# Kopfh_rerverst_rker_DAC_Board_CP2114_Rev.net
KiCad netlist of a schematic drawn in EAGLE
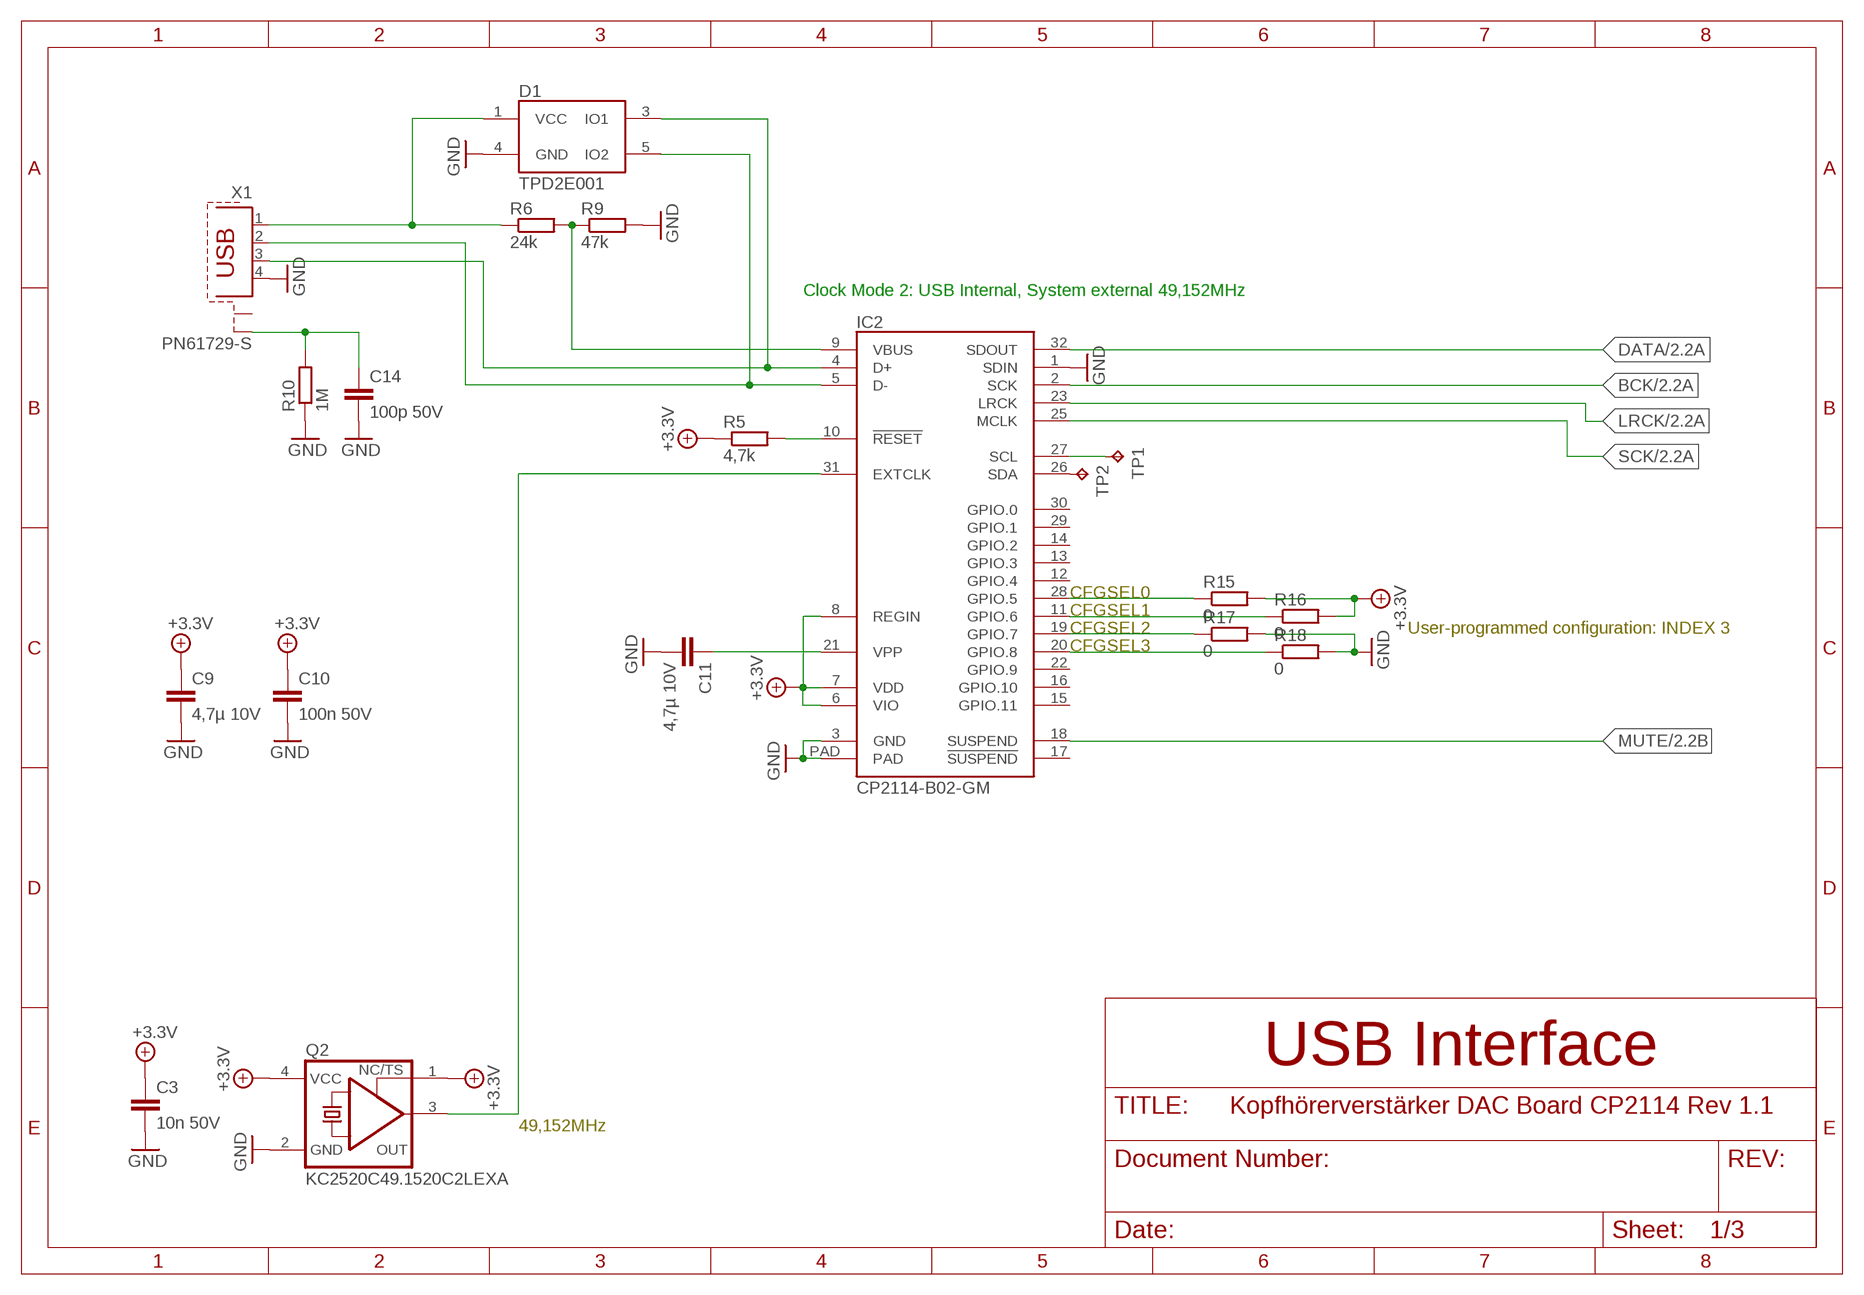
[diagram p0: schematic, sheet 1]
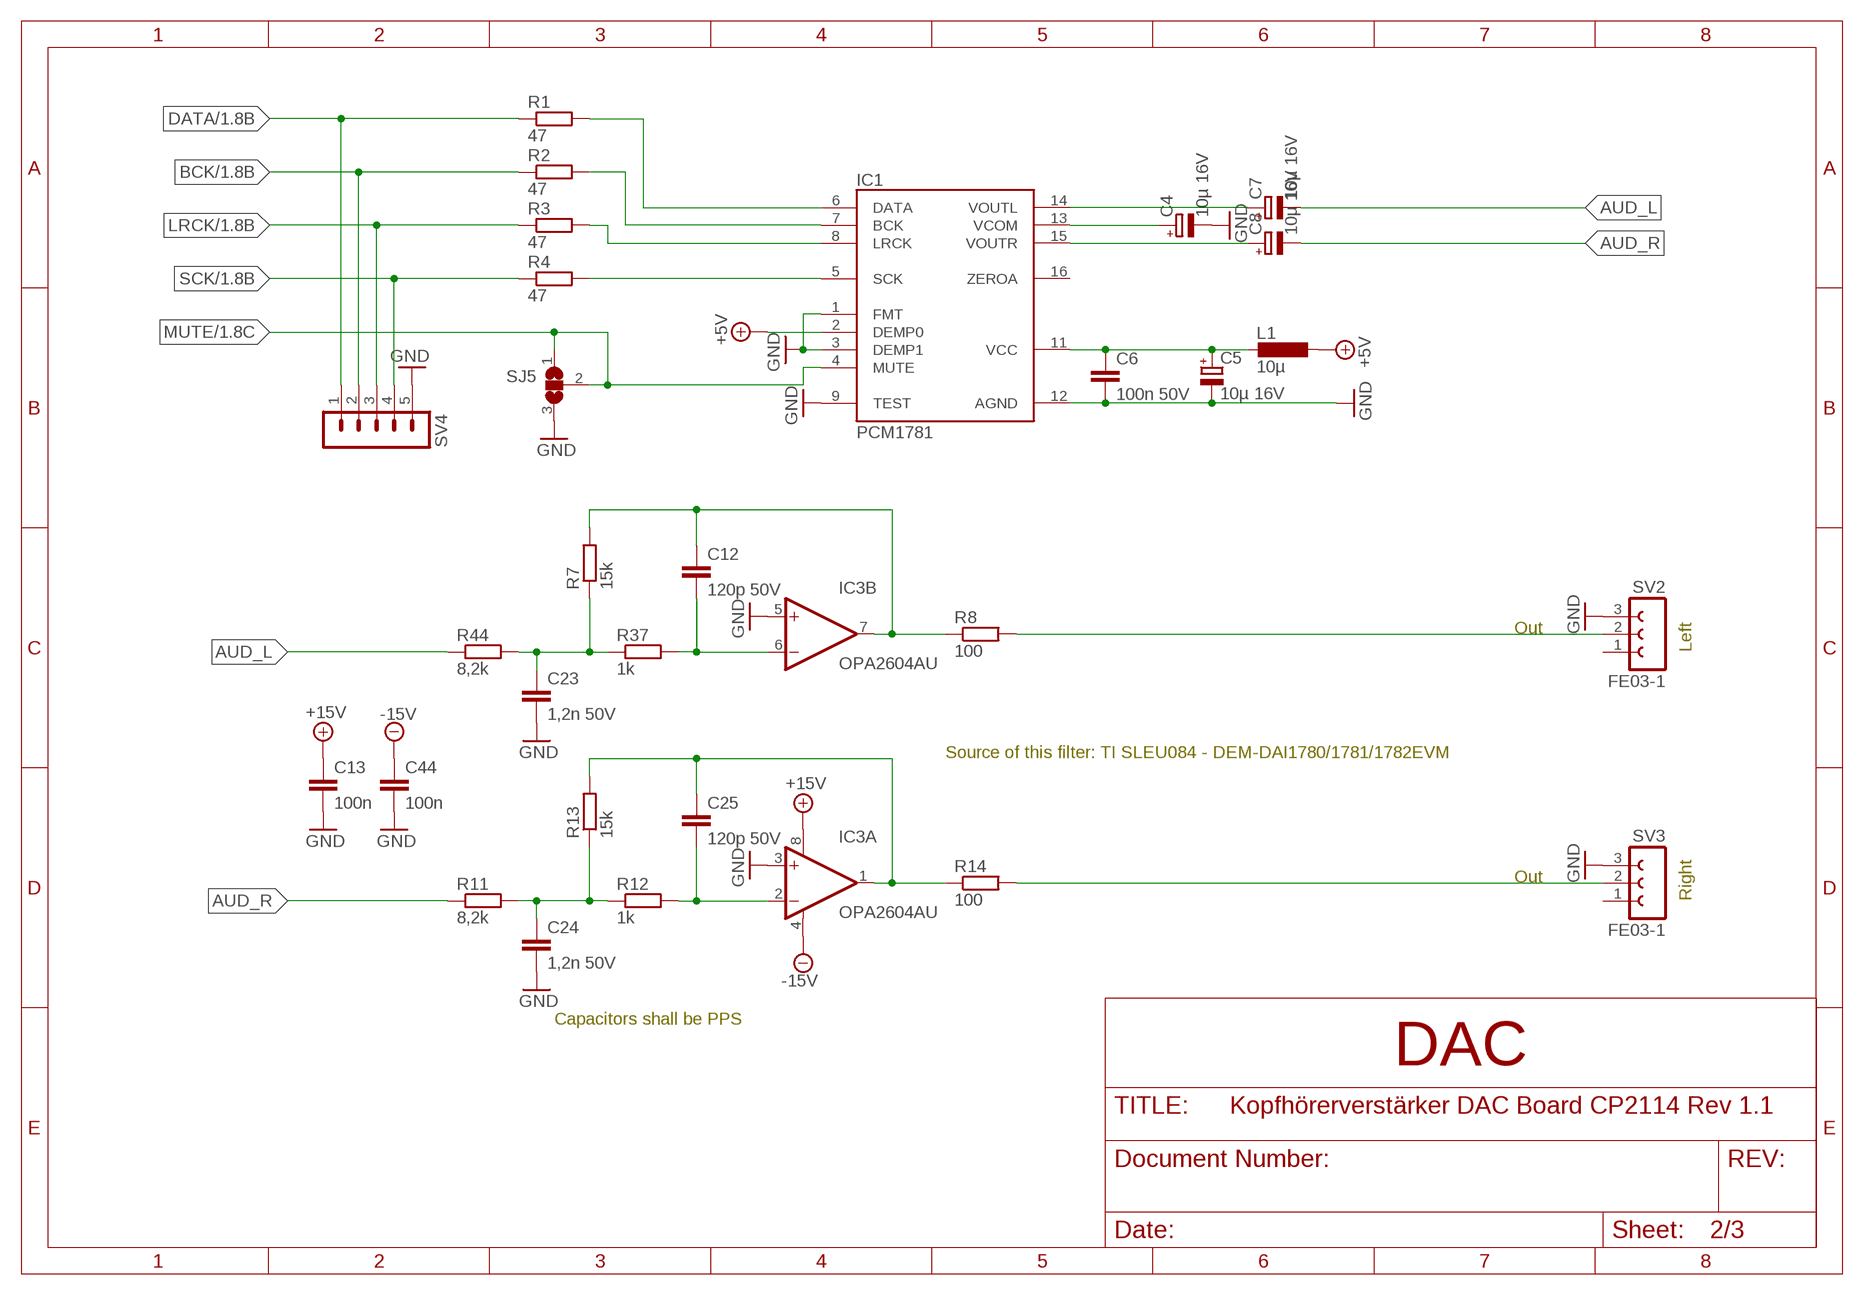
[diagram p1: schematic, sheet 2]
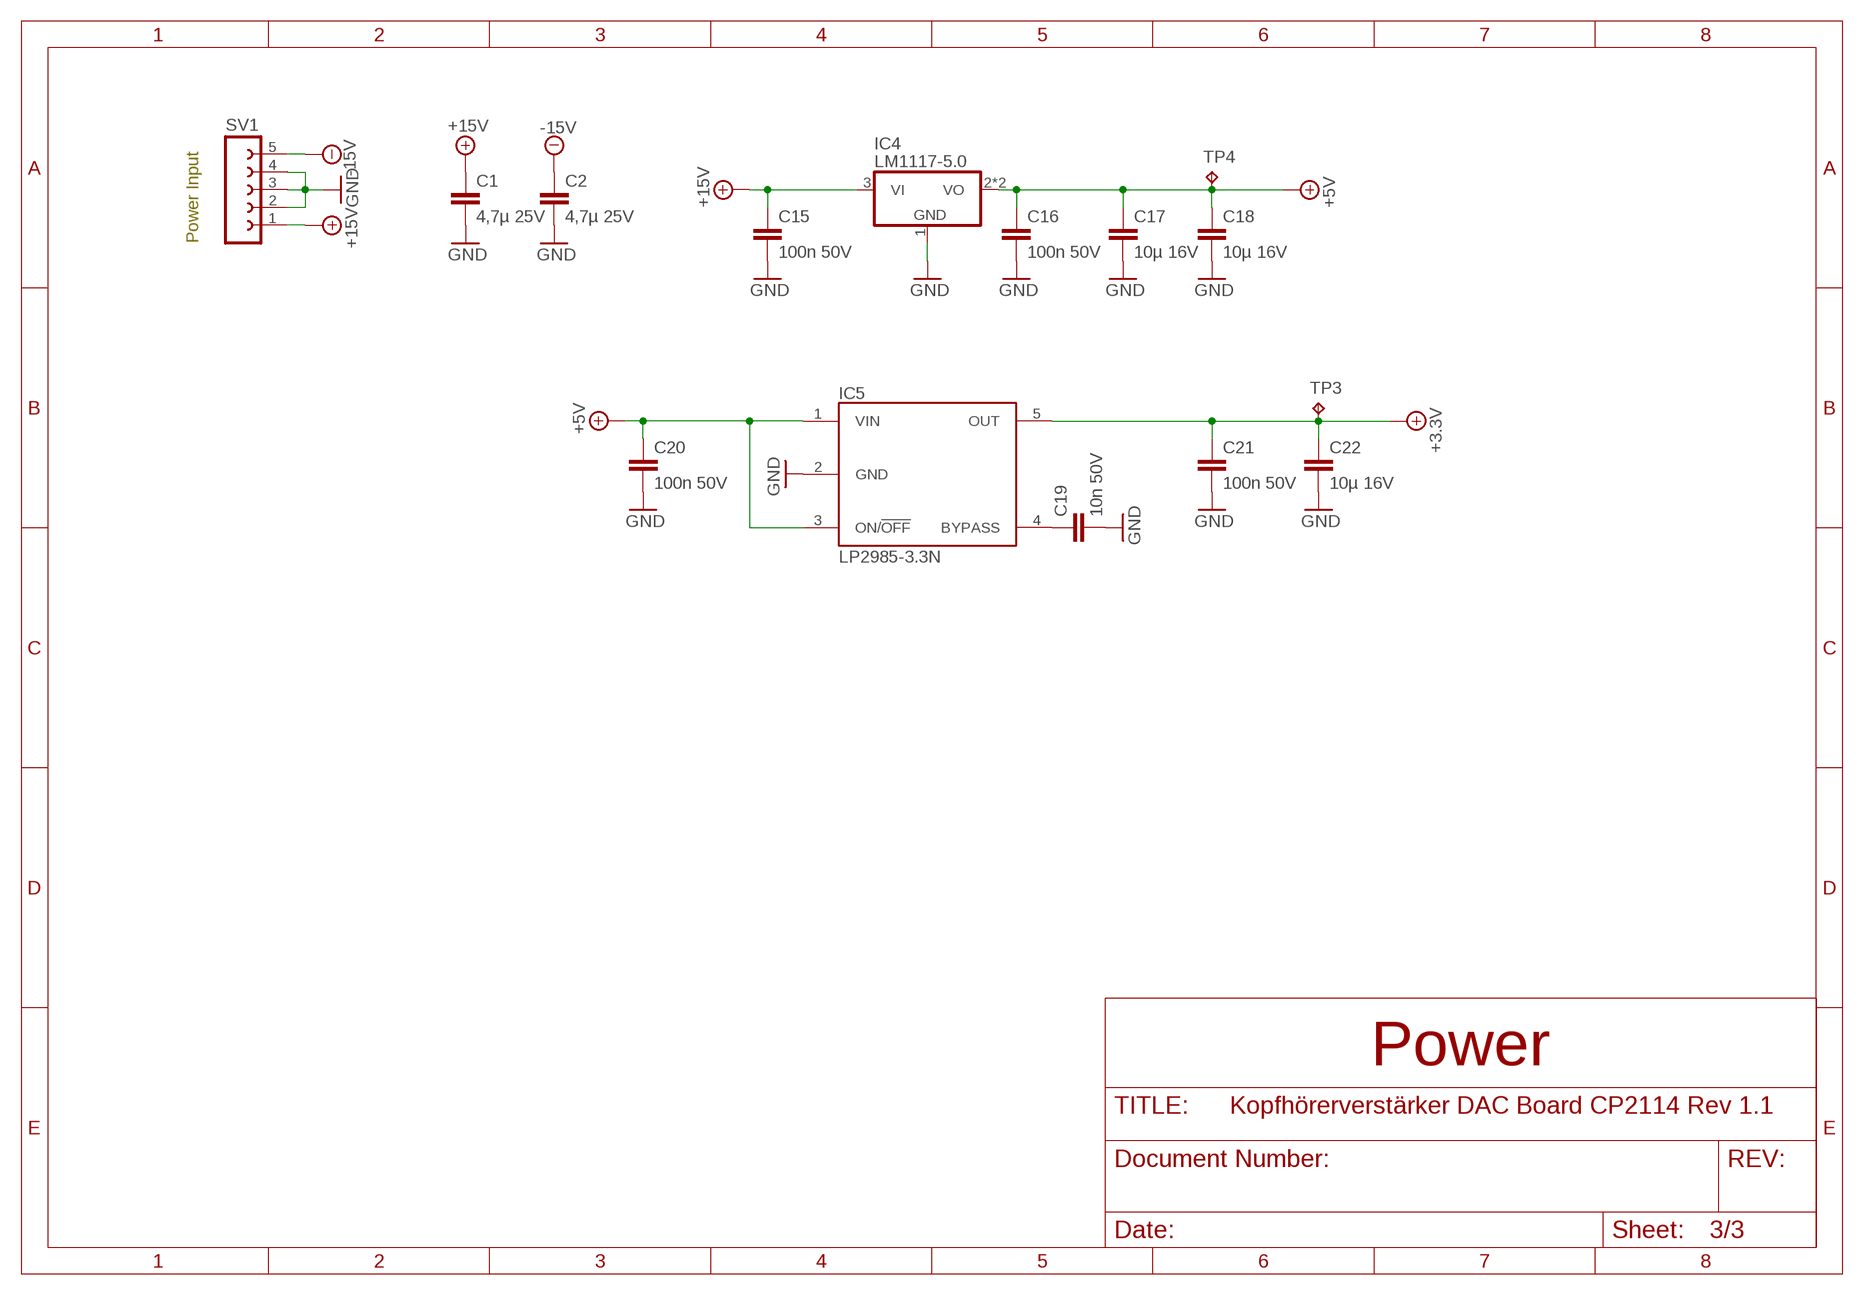
[diagram p2: schematic, sheet 3]

(export (version "E")
  (design (tool "Eeschema 10.0.6"))
  (components
    (comp (ref "C3")
      (value "10n 50V")
      (footprint "eagle-import:C0805")
      (libsource (lib "eagle-import") (part "C-EUC0805"))
    )
    (comp (ref "C9")
      (value "4,7µ 10V")
      (footprint "eagle-import:C0805")
      (libsource (lib "eagle-import") (part "C-EUC0805"))
    )
    (comp (ref "C10")
      (value "100n 50V")
      (footprint "eagle-import:C0805")
      (libsource (lib "eagle-import") (part "C-EUC0805"))
    )
    (comp (ref "C11")
      (value "4,7µ 10V")
      (footprint "eagle-import:C0805")
      (libsource (lib "eagle-import") (part "C-EUC0805"))
    )
    (comp (ref "C14")
      (value "100p 50V")
      (footprint "eagle-import:C0805")
      (libsource (lib "eagle-import") (part "C-EUC0805"))
    )
    (comp (ref "D1")
      (value "TPD2E001")
      (footprint "eagle-import:SOT-5X3_R-PDSO-N5-DRL")
      (libsource (lib "eagle-import") (part "TPD2E001"))
    )
    (comp (ref "IC2")
      (value "CP2114-B02-GM")
      (footprint "eagle-import:QFN32")
      (libsource (lib "eagle-import") (part "CP2114-B02-GM"))
    )
    (comp (ref "Q2")
      (value "KC2520C49.1520C2LEXA")
      (footprint "eagle-import:2.5X2.0")
      (libsource (lib "eagle-import") (part "XO-2,5X2,0"))
    )
    (comp (ref "R5")
      (value "4,7k")
      (footprint "eagle-import:R0805")
      (libsource (lib "eagle-import") (part "R-EU_R0805"))
    )
    (comp (ref "R6")
      (value "24k")
      (footprint "eagle-import:R0805")
      (libsource (lib "eagle-import") (part "R-EU_R0805"))
    )
    (comp (ref "R9")
      (value "47k")
      (footprint "eagle-import:R0805")
      (libsource (lib "eagle-import") (part "R-EU_R0805"))
    )
    (comp (ref "R10")
      (value "1M")
      (footprint "eagle-import:R0805")
      (libsource (lib "eagle-import") (part "R-EU_R0805"))
    )
    (comp (ref "R15")
      (value "0")
      (footprint "eagle-import:R0805")
      (libsource (lib "eagle-import") (part "R-EU_R0805"))
    )
    (comp (ref "R16")
      (value "0")
      (footprint "eagle-import:R0805")
      (libsource (lib "eagle-import") (part "R-EU_R0805"))
    )
    (comp (ref "R17")
      (value "0")
      (footprint "eagle-import:R0805")
      (libsource (lib "eagle-import") (part "R-EU_R0805"))
    )
    (comp (ref "R18")
      (value "0")
      (footprint "eagle-import:R0805")
      (libsource (lib "eagle-import") (part "R-EU_R0805"))
    )
    (comp (ref "TP1")
      (value "TPTP10R")
      (footprint "eagle-import:TP10R")
      (libsource (lib "eagle-import") (part "TPTP10R"))
    )
    (comp (ref "TP2")
      (value "TPTP10R")
      (footprint "eagle-import:TP10R")
      (libsource (lib "eagle-import") (part "TPTP10R"))
    )
    (comp (ref "X1")
      (value "PN61729-S")
      (footprint "eagle-import:PN61729-S")
      (libsource (lib "eagle-import") (part "PN61729-S"))
    )
    (comp (ref "C1")
      (value "4,7µ 25V")
      (footprint "eagle-import:C0805")
      (libsource (lib "eagle-import") (part "C-EUC0805"))
    )
    (comp (ref "C2")
      (value "4,7µ 25V")
      (footprint "eagle-import:C0805")
      (libsource (lib "eagle-import") (part "C-EUC0805"))
    )
    (comp (ref "C15")
      (value "100n 50V")
      (footprint "eagle-import:C0805")
      (libsource (lib "eagle-import") (part "C-EUC0805"))
    )
    (comp (ref "C16")
      (value "100n 50V")
      (footprint "eagle-import:C0805")
      (libsource (lib "eagle-import") (part "C-EUC0805"))
    )
    (comp (ref "C17")
      (value "10µ 16V")
      (footprint "eagle-import:C0805")
      (libsource (lib "eagle-import") (part "C-EUC0805"))
    )
    (comp (ref "C18")
      (value "10µ 16V")
      (footprint "eagle-import:C0805")
      (libsource (lib "eagle-import") (part "C-EUC0805"))
    )
    (comp (ref "C19")
      (value "10n 50V")
      (footprint "eagle-import:C0805")
      (libsource (lib "eagle-import") (part "C-EUC0805"))
    )
    (comp (ref "C20")
      (value "100n 50V")
      (footprint "eagle-import:C0805")
      (libsource (lib "eagle-import") (part "C-EUC0805"))
    )
    (comp (ref "C21")
      (value "100n 50V")
      (footprint "eagle-import:C0805")
      (libsource (lib "eagle-import") (part "C-EUC0805"))
    )
    (comp (ref "C22")
      (value "10µ 16V")
      (footprint "eagle-import:C0805")
      (libsource (lib "eagle-import") (part "C-EUC0805"))
    )
    (comp (ref "IC4")
      (value "LM1117-5.0")
      (footprint "eagle-import:SOT223")
      (libsource (lib "eagle-import") (part "LM1117-5.0"))
    )
    (comp (ref "IC5")
      (value "LP2985-3.3N")
      (footprint "eagle-import:SOT23-DBV")
      (libsource (lib "eagle-import") (part "LP2985N-3.3"))
    )
    (comp (ref "SV1")
      (value "FE05-1")
      (footprint "eagle-import:FE05-1")
      (libsource (lib "eagle-import") (part "FE05-1"))
    )
    (comp (ref "TP3")
      (value "TPTP15R")
      (footprint "eagle-import:TP15R")
      (libsource (lib "eagle-import") (part "TPTP15R"))
    )
    (comp (ref "TP4")
      (value "TPTP15R")
      (footprint "eagle-import:TP15R")
      (libsource (lib "eagle-import") (part "TPTP15R"))
    )
    (comp (ref "C4")
      (value "10µ 16V")
      (footprint "eagle-import:E2,5-5")
      (libsource (lib "eagle-import") (part "CPOL-EUE2.5-5"))
    )
    (comp (ref "C5")
      (value "10µ 16V")
      (footprint "eagle-import:E2,5-5")
      (libsource (lib "eagle-import") (part "CPOL-EUE2.5-5"))
    )
    (comp (ref "C6")
      (value "100n 50V")
      (footprint "eagle-import:C0805")
      (libsource (lib "eagle-import") (part "C-EUC0805"))
    )
    (comp (ref "C7")
      (value "10µ 16V")
      (footprint "eagle-import:E2,5-5")
      (libsource (lib "eagle-import") (part "CPOL-EUE2.5-5"))
    )
    (comp (ref "C8")
      (value "10µ 16V")
      (footprint "eagle-import:E2,5-5")
      (libsource (lib "eagle-import") (part "CPOL-EUE2.5-5"))
    )
    (comp (ref "C12")
      (value "120p 50V")
      (footprint "eagle-import:C0805")
      (libsource (lib "eagle-import") (part "C-EUC0805"))
    )
    (comp (ref "C13")
      (value "100n")
      (footprint "eagle-import:C0805")
      (libsource (lib "eagle-import") (part "C-EUC0805"))
    )
    (comp (ref "C23")
      (value "1,2n 50V")
      (footprint "eagle-import:C0805")
      (libsource (lib "eagle-import") (part "C-EUC0805"))
    )
    (comp (ref "C24")
      (value "1,2n 50V")
      (footprint "eagle-import:C0805")
      (libsource (lib "eagle-import") (part "C-EUC0805"))
    )
    (comp (ref "C25")
      (value "120p 50V")
      (footprint "eagle-import:C0805")
      (libsource (lib "eagle-import") (part "C-EUC0805"))
    )
    (comp (ref "C44")
      (value "100n")
      (footprint "eagle-import:C0805")
      (libsource (lib "eagle-import") (part "C-EUC0805"))
    )
    (comp (ref "IC1")
      (value "PCM1781")
      (footprint "eagle-import:PW_R-PDSO-G16")
      (libsource (lib "eagle-import") (part "PCM1781"))
    )
    (comp (ref "IC3")
      (value "OPA2604AU")
      (footprint "eagle-import:SO08")
      (libsource (lib "eagle-import") (part "OPA2604AU"))
    )
    (comp (ref "L1")
      (value "10µ")
      (footprint "eagle-import:L0805")
      (libsource (lib "eagle-import") (part "L-EUL0805"))
    )
    (comp (ref "R1")
      (value "47")
      (footprint "eagle-import:R0805")
      (libsource (lib "eagle-import") (part "R-EU_R0805"))
    )
    (comp (ref "R2")
      (value "47")
      (footprint "eagle-import:R0805")
      (libsource (lib "eagle-import") (part "R-EU_R0805"))
    )
    (comp (ref "R3")
      (value "47")
      (footprint "eagle-import:R0805")
      (libsource (lib "eagle-import") (part "R-EU_R0805"))
    )
    (comp (ref "R4")
      (value "47")
      (footprint "eagle-import:R0805")
      (libsource (lib "eagle-import") (part "R-EU_R0805"))
    )
    (comp (ref "R7")
      (value "15k")
      (footprint "eagle-import:R0805")
      (libsource (lib "eagle-import") (part "R-EU_R0805"))
    )
    (comp (ref "R8")
      (value "100")
      (footprint "eagle-import:R0805")
      (libsource (lib "eagle-import") (part "R-EU_R0805"))
    )
    (comp (ref "R11")
      (value "8,2k")
      (footprint "eagle-import:R0805")
      (libsource (lib "eagle-import") (part "R-EU_R0805"))
    )
    (comp (ref "R12")
      (value "1k")
      (footprint "eagle-import:R0805")
      (libsource (lib "eagle-import") (part "R-EU_R0805"))
    )
    (comp (ref "R13")
      (value "15k")
      (footprint "eagle-import:R0805")
      (libsource (lib "eagle-import") (part "R-EU_R0805"))
    )
    (comp (ref "R14")
      (value "100")
      (footprint "eagle-import:R0805")
      (libsource (lib "eagle-import") (part "R-EU_R0805"))
    )
    (comp (ref "R37")
      (value "1k")
      (footprint "eagle-import:R0805")
      (libsource (lib "eagle-import") (part "R-EU_R0805"))
    )
    (comp (ref "R44")
      (value "8,2k")
      (footprint "eagle-import:R0805")
      (libsource (lib "eagle-import") (part "R-EU_R0805"))
    )
    (comp (ref "SJ5")
      (value "SJ2W")
      (footprint "eagle-import:SJ_2")
      (libsource (lib "eagle-import") (part "SJ2W"))
    )
    (comp (ref "SV2")
      (value "FE03-1")
      (footprint "eagle-import:FE03-1")
      (libsource (lib "eagle-import") (part "FE03-1"))
    )
    (comp (ref "SV3")
      (value "FE03-1")
      (footprint "eagle-import:FE03-1")
      (libsource (lib "eagle-import") (part "FE03-1"))
    )
    (comp (ref "SV4")
      (value "MA05-1")
      (footprint "eagle-import:MA05-1")
      (libsource (lib "eagle-import") (part "MA05-1"))
    )
  )
  (nets
    (net (code "1") (name "+3,3V") (class "Default")
      (node (ref "C10") (pin "1") (pinfunction "1_1") (pintype "passive"))
      (node (ref "C21") (pin "1") (pinfunction "1_1") (pintype "passive"))
      (node (ref "C22") (pin "1") (pinfunction "1_1") (pintype "passive"))
      (node (ref "C3") (pin "1") (pinfunction "1_1") (pintype "passive"))
      (node (ref "C9") (pin "1") (pinfunction "1_1") (pintype "passive"))
      (node (ref "IC2") (pin "6") (pinfunction "VIO_6") (pintype "bidirectional"))
      (node (ref "IC2") (pin "7") (pinfunction "VDD_7") (pintype "bidirectional"))
      (node (ref "IC2") (pin "8") (pinfunction "REGIN_8") (pintype "bidirectional"))
      (node (ref "IC5") (pin "5") (pinfunction "OUT_5") (pintype "bidirectional"))
      (node (ref "Q2") (pin "1") (pinfunction "TS_1") (pintype "passive"))
      (node (ref "Q2") (pin "4") (pinfunction "VCC_4") (pintype "power_in"))
      (node (ref "R15") (pin "2") (pinfunction "2_2") (pintype "passive"))
      (node (ref "R16") (pin "2") (pinfunction "2_2") (pintype "passive"))
      (node (ref "R5") (pin "1") (pinfunction "1_1") (pintype "passive"))
      (node (ref "TP3") (pin "TP") (pinfunction "TP_TP") (pintype "input"))
    )
    (net (code "2") (name "+5V") (class "Default")
      (node (ref "C16") (pin "1") (pinfunction "1_1") (pintype "passive"))
      (node (ref "C17") (pin "1") (pinfunction "1_1") (pintype "passive"))
      (node (ref "C18") (pin "1") (pinfunction "1_1") (pintype "passive"))
      (node (ref "C20") (pin "1") (pinfunction "1_1") (pintype "passive"))
      (node (ref "IC1") (pin "2") (pinfunction "DEMP0_2") (pintype "bidirectional"))
      (node (ref "IC4") (pin "2") (pinfunction "VO_2") (pintype "passive"))
      (node (ref "IC4") (pin "4") (pinfunction "VO_4") (pintype "passive"))
      (node (ref "IC5") (pin "1") (pinfunction "VIN_1") (pintype "bidirectional"))
      (node (ref "IC5") (pin "3") (pinfunction "ON/~{OFF}_3") (pintype "bidirectional"))
      (node (ref "L1") (pin "1") (pinfunction "1_1") (pintype "passive"))
      (node (ref "TP4") (pin "TP") (pinfunction "TP_TP") (pintype "input"))
    )
    (net (code "3") (name "+15V") (class "Default")
      (node (ref "C1") (pin "1") (pinfunction "1_1") (pintype "passive"))
      (node (ref "C13") (pin "1") (pinfunction "1_1") (pintype "passive"))
      (node (ref "C15") (pin "1") (pinfunction "1_1") (pintype "passive"))
      (node (ref "IC3") (pin "8") (pinfunction "V+_8") (pintype "power_in"))
      (node (ref "IC4") (pin "3") (pinfunction "VI_3") (pintype "input"))
      (node (ref "SV1") (pin "1") (pinfunction "1_1") (pintype "passive"))
    )
    (net (code "4") (name "-15V") (class "Default")
      (node (ref "C2") (pin "1") (pinfunction "1_1") (pintype "passive"))
      (node (ref "C44") (pin "1") (pinfunction "1_1") (pintype "passive"))
      (node (ref "IC3") (pin "4") (pinfunction "V-_4") (pintype "power_in"))
      (node (ref "SV1") (pin "5") (pinfunction "5_5") (pintype "passive"))
    )
    (net (code "5") (name "AUD_L") (class "Default")
      (node (ref "C7") (pin "-") (pinfunction "-_-") (pintype "passive"))
      (node (ref "R44") (pin "1") (pinfunction "1_1") (pintype "passive"))
    )
    (net (code "6") (name "AUD_R") (class "Default")
      (node (ref "C8") (pin "-") (pinfunction "-_-") (pintype "passive"))
      (node (ref "R11") (pin "1") (pinfunction "1_1") (pintype "passive"))
    )
    (net (code "7") (name "BCK") (class "Default")
      (node (ref "IC2") (pin "2") (pinfunction "SCK_2") (pintype "bidirectional"))
      (node (ref "R2") (pin "1") (pinfunction "1_1") (pintype "passive"))
      (node (ref "SV4") (pin "2") (pinfunction "2_2") (pintype "passive"))
    )
    (net (code "8") (name "DATA") (class "Default")
      (node (ref "IC2") (pin "32") (pinfunction "SDOUT_32") (pintype "bidirectional"))
      (node (ref "R1") (pin "1") (pinfunction "1_1") (pintype "passive"))
      (node (ref "SV4") (pin "1") (pinfunction "1_1") (pintype "passive"))
    )
    (net (code "9") (name "GND") (class "Default")
      (node (ref "C1") (pin "2") (pinfunction "2_2") (pintype "passive"))
      (node (ref "C10") (pin "2") (pinfunction "2_2") (pintype "passive"))
      (node (ref "C11") (pin "2") (pinfunction "2_2") (pintype "passive"))
      (node (ref "C13") (pin "2") (pinfunction "2_2") (pintype "passive"))
      (node (ref "C14") (pin "2") (pinfunction "2_2") (pintype "passive"))
      (node (ref "C15") (pin "2") (pinfunction "2_2") (pintype "passive"))
      (node (ref "C16") (pin "2") (pinfunction "2_2") (pintype "passive"))
      (node (ref "C17") (pin "2") (pinfunction "2_2") (pintype "passive"))
      (node (ref "C18") (pin "2") (pinfunction "2_2") (pintype "passive"))
      (node (ref "C19") (pin "2") (pinfunction "2_2") (pintype "passive"))
      (node (ref "C2") (pin "2") (pinfunction "2_2") (pintype "passive"))
      (node (ref "C20") (pin "2") (pinfunction "2_2") (pintype "passive"))
      (node (ref "C21") (pin "2") (pinfunction "2_2") (pintype "passive"))
      (node (ref "C22") (pin "2") (pinfunction "2_2") (pintype "passive"))
      (node (ref "C23") (pin "2") (pinfunction "2_2") (pintype "passive"))
      (node (ref "C24") (pin "2") (pinfunction "2_2") (pintype "passive"))
      (node (ref "C3") (pin "2") (pinfunction "2_2") (pintype "passive"))
      (node (ref "C4") (pin "-") (pinfunction "-_-") (pintype "passive"))
      (node (ref "C44") (pin "2") (pinfunction "2_2") (pintype "passive"))
      (node (ref "C5") (pin "-") (pinfunction "-_-") (pintype "passive"))
      (node (ref "C6") (pin "2") (pinfunction "2_2") (pintype "passive"))
      (node (ref "C9") (pin "2") (pinfunction "2_2") (pintype "passive"))
      (node (ref "D1") (pin "4") (pinfunction "GND_4") (pintype "bidirectional"))
      (node (ref "IC1") (pin "1") (pinfunction "FMT_1") (pintype "bidirectional"))
      (node (ref "IC1") (pin "12") (pinfunction "AGND_12") (pintype "bidirectional"))
      (node (ref "IC1") (pin "3") (pinfunction "DEMP1_3") (pintype "bidirectional"))
      (node (ref "IC1") (pin "9") (pinfunction "TEST_9") (pintype "bidirectional"))
      (node (ref "IC2") (pin "1") (pinfunction "SDIN_1") (pintype "bidirectional"))
      (node (ref "IC2") (pin "3") (pinfunction "GND_3") (pintype "bidirectional"))
      (node (ref "IC2") (pin "PAD") (pinfunction "PAD_PAD") (pintype "bidirectional"))
      (node (ref "IC3") (pin "3") (pinfunction "+IN_3") (pintype "input"))
      (node (ref "IC3") (pin "5") (pinfunction "+IN_5") (pintype "input"))
      (node (ref "IC4") (pin "1") (pinfunction "GND_1") (pintype "passive"))
      (node (ref "IC5") (pin "2") (pinfunction "GND_2") (pintype "bidirectional"))
      (node (ref "Q2") (pin "2") (pinfunction "GND_2") (pintype "power_in"))
      (node (ref "R10") (pin "1") (pinfunction "1_1") (pintype "passive"))
      (node (ref "R17") (pin "2") (pinfunction "2_2") (pintype "passive"))
      (node (ref "R18") (pin "2") (pinfunction "2_2") (pintype "passive"))
      (node (ref "R9") (pin "2") (pinfunction "2_2") (pintype "passive"))
      (node (ref "SJ5") (pin "3") (pinfunction "3_3") (pintype "passive"))
      (node (ref "SV1") (pin "2") (pinfunction "2_2") (pintype "passive"))
      (node (ref "SV1") (pin "3") (pinfunction "3_3") (pintype "passive"))
      (node (ref "SV1") (pin "4") (pinfunction "4_4") (pintype "passive"))
      (node (ref "SV2") (pin "3") (pinfunction "3_3") (pintype "passive"))
      (node (ref "SV3") (pin "3") (pinfunction "3_3") (pintype "passive"))
      (node (ref "SV4") (pin "5") (pinfunction "5_5") (pintype "passive"))
      (node (ref "X1") (pin "4") (pinfunction "4_4") (pintype "passive"))
    )
    (net (code "10") (name "LRCK") (class "Default")
      (node (ref "IC2") (pin "23") (pinfunction "LRCK_23") (pintype "bidirectional"))
      (node (ref "R3") (pin "1") (pinfunction "1_1") (pintype "passive"))
      (node (ref "SV4") (pin "3") (pinfunction "3_3") (pintype "passive"))
    )
    (net (code "11") (name "MUTE") (class "Default")
      (node (ref "IC1") (pin "4") (pinfunction "MUTE_4") (pintype "bidirectional"))
      (node (ref "IC2") (pin "18") (pinfunction "SUSPEND_18") (pintype "bidirectional"))
      (node (ref "SJ5") (pin "1") (pinfunction "1_1") (pintype "passive"))
      (node (ref "SJ5") (pin "2") (pinfunction "2_2") (pintype "passive"))
    )
    (net (code "12") (name "Net-(C14-Pad1)") (class "Default")
      (node (ref "C14") (pin "1") (pinfunction "1_1") (pintype "passive"))
      (node (ref "R10") (pin "2") (pinfunction "2_2") (pintype "passive"))
      (node (ref "X1") (pin "S2") (pinfunction "S2_S2") (pintype "passive"))
    )
    (net (code "13") (name "Net-(C23-Pad1)") (class "Default")
      (node (ref "C23") (pin "1") (pinfunction "1_1") (pintype "passive"))
      (node (ref "R37") (pin "1") (pinfunction "1_1") (pintype "passive"))
      (node (ref "R44") (pin "2") (pinfunction "2_2") (pintype "passive"))
      (node (ref "R7") (pin "1") (pinfunction "1_1") (pintype "passive"))
    )
    (net (code "14") (name "Net-(C24-Pad1)") (class "Default")
      (node (ref "C24") (pin "1") (pinfunction "1_1") (pintype "passive"))
      (node (ref "R11") (pin "2") (pinfunction "2_2") (pintype "passive"))
      (node (ref "R12") (pin "1") (pinfunction "1_1") (pintype "passive"))
      (node (ref "R13") (pin "1") (pinfunction "1_1") (pintype "passive"))
    )
    (net (code "15") (name "Net-(D1-IO1)") (class "Default")
      (node (ref "D1") (pin "3") (pinfunction "IO1_3") (pintype "bidirectional"))
      (node (ref "IC2") (pin "4") (pinfunction "D+_4") (pintype "bidirectional"))
      (node (ref "X1") (pin "3") (pinfunction "3_3") (pintype "passive"))
    )
    (net (code "16") (name "Net-(D1-IO2)") (class "Default")
      (node (ref "D1") (pin "5") (pinfunction "IO2_5") (pintype "bidirectional"))
      (node (ref "IC2") (pin "5") (pinfunction "D-_5") (pintype "bidirectional"))
      (node (ref "X1") (pin "2") (pinfunction "2_2") (pintype "passive"))
    )
    (net (code "17") (name "Net-(D1-VCC)") (class "Default")
      (node (ref "D1") (pin "1") (pinfunction "VCC_1") (pintype "bidirectional"))
      (node (ref "R6") (pin "1") (pinfunction "1_1") (pintype "passive"))
      (node (ref "X1") (pin "1") (pinfunction "1_1") (pintype "passive"))
    )
    (net (code "18") (name "Net-(IC1-BCK)") (class "Default")
      (node (ref "IC1") (pin "7") (pinfunction "BCK_7") (pintype "bidirectional"))
      (node (ref "R2") (pin "2") (pinfunction "2_2") (pintype "passive"))
    )
    (net (code "19") (name "Net-(IC1-DATA)") (class "Default")
      (node (ref "IC1") (pin "6") (pinfunction "DATA_6") (pintype "bidirectional"))
      (node (ref "R1") (pin "2") (pinfunction "2_2") (pintype "passive"))
    )
    (net (code "20") (name "Net-(IC1-LRCK)") (class "Default")
      (node (ref "IC1") (pin "8") (pinfunction "LRCK_8") (pintype "bidirectional"))
      (node (ref "R3") (pin "2") (pinfunction "2_2") (pintype "passive"))
    )
    (net (code "21") (name "Net-(IC1-SCK)") (class "Default")
      (node (ref "IC1") (pin "5") (pinfunction "SCK_5") (pintype "bidirectional"))
      (node (ref "R4") (pin "2") (pinfunction "2_2") (pintype "passive"))
    )
    (net (code "22") (name "Net-(IC1-VCC)") (class "Default")
      (node (ref "C5") (pin "+") (pinfunction "+_+") (pintype "passive"))
      (node (ref "C6") (pin "1") (pinfunction "1_1") (pintype "passive"))
      (node (ref "IC1") (pin "11") (pinfunction "VCC_11") (pintype "bidirectional"))
      (node (ref "L1") (pin "2") (pinfunction "2_2") (pintype "passive"))
    )
    (net (code "23") (name "Net-(IC1-VCOM)") (class "Default")
      (node (ref "C4") (pin "+") (pinfunction "+_+") (pintype "passive"))
      (node (ref "IC1") (pin "13") (pinfunction "VCOM_13") (pintype "bidirectional"))
    )
    (net (code "24") (name "Net-(IC1-VOUTL)") (class "Default")
      (node (ref "C7") (pin "+") (pinfunction "+_+") (pintype "passive"))
      (node (ref "IC1") (pin "14") (pinfunction "VOUTL_14") (pintype "bidirectional"))
    )
    (net (code "25") (name "Net-(IC1-VOUTR)") (class "Default")
      (node (ref "C8") (pin "+") (pinfunction "+_+") (pintype "passive"))
      (node (ref "IC1") (pin "15") (pinfunction "VOUTR_15") (pintype "bidirectional"))
    )
    (net (code "26") (name "Net-(IC2-EXTCLK)") (class "Default")
      (node (ref "IC2") (pin "31") (pinfunction "EXTCLK_31") (pintype "bidirectional"))
      (node (ref "Q2") (pin "3") (pinfunction "OUT_3") (pintype "output"))
    )
    (net (code "27") (name "Net-(IC2-GPIO.5)") (class "Default")
      (node (ref "IC2") (pin "28") (pinfunction "GPIO.5_28") (pintype "bidirectional"))
      (node (ref "R15") (pin "1") (pinfunction "1_1") (pintype "passive"))
    )
    (net (code "28") (name "Net-(IC2-GPIO.6)") (class "Default")
      (node (ref "IC2") (pin "11") (pinfunction "GPIO.6_11") (pintype "bidirectional"))
      (node (ref "R16") (pin "1") (pinfunction "1_1") (pintype "passive"))
    )
    (net (code "29") (name "Net-(IC2-GPIO.7)") (class "Default")
      (node (ref "IC2") (pin "19") (pinfunction "GPIO.7_19") (pintype "bidirectional"))
      (node (ref "R17") (pin "1") (pinfunction "1_1") (pintype "passive"))
    )
    (net (code "30") (name "Net-(IC2-GPIO.8)") (class "Default")
      (node (ref "IC2") (pin "20") (pinfunction "GPIO.8_20") (pintype "bidirectional"))
      (node (ref "R18") (pin "1") (pinfunction "1_1") (pintype "passive"))
    )
    (net (code "31") (name "Net-(IC2-SCL)") (class "Default")
      (node (ref "IC2") (pin "27") (pinfunction "SCL_27") (pintype "bidirectional"))
      (node (ref "TP1") (pin "TP") (pinfunction "TP_TP") (pintype "input"))
    )
    (net (code "32") (name "Net-(IC2-SDA)") (class "Default")
      (node (ref "IC2") (pin "26") (pinfunction "SDA_26") (pintype "bidirectional"))
      (node (ref "TP2") (pin "TP") (pinfunction "TP_TP") (pintype "input"))
    )
    (net (code "33") (name "Net-(IC2-VBUS)") (class "Default")
      (node (ref "IC2") (pin "9") (pinfunction "VBUS_9") (pintype "bidirectional"))
      (node (ref "R6") (pin "2") (pinfunction "2_2") (pintype "passive"))
      (node (ref "R9") (pin "1") (pinfunction "1_1") (pintype "passive"))
    )
    (net (code "34") (name "Net-(IC2-VPP)") (class "Default")
      (node (ref "C11") (pin "1") (pinfunction "1_1") (pintype "passive"))
      (node (ref "IC2") (pin "21") (pinfunction "VPP_21") (pintype "bidirectional"))
    )
    (net (code "35") (name "Net-(IC2-~{RESET})") (class "Default")
      (node (ref "IC2") (pin "10") (pinfunction "~{RESET}_10") (pintype "bidirectional"))
      (node (ref "R5") (pin "2") (pinfunction "2_2") (pintype "passive"))
    )
    (net (code "36") (name "Net-(IC3A--IN)") (class "Default")
      (node (ref "C25") (pin "2") (pinfunction "2_2") (pintype "passive"))
      (node (ref "IC3") (pin "2") (pinfunction "-IN_2") (pintype "input"))
      (node (ref "R12") (pin "2") (pinfunction "2_2") (pintype "passive"))
    )
    (net (code "37") (name "Net-(IC3A-OUT)") (class "Default")
      (node (ref "C25") (pin "1") (pinfunction "1_1") (pintype "passive"))
      (node (ref "IC3") (pin "1") (pinfunction "OUT_1") (pintype "output"))
      (node (ref "R13") (pin "2") (pinfunction "2_2") (pintype "passive"))
      (node (ref "R14") (pin "1") (pinfunction "1_1") (pintype "passive"))
    )
    (net (code "38") (name "Net-(IC3B--IN)") (class "Default")
      (node (ref "C12") (pin "2") (pinfunction "2_2") (pintype "passive"))
      (node (ref "IC3") (pin "6") (pinfunction "-IN_6") (pintype "input"))
      (node (ref "R37") (pin "2") (pinfunction "2_2") (pintype "passive"))
    )
    (net (code "39") (name "Net-(IC3B-OUT)") (class "Default")
      (node (ref "C12") (pin "1") (pinfunction "1_1") (pintype "passive"))
      (node (ref "IC3") (pin "7") (pinfunction "OUT_7") (pintype "output"))
      (node (ref "R7") (pin "2") (pinfunction "2_2") (pintype "passive"))
      (node (ref "R8") (pin "1") (pinfunction "1_1") (pintype "passive"))
    )
    (net (code "40") (name "Net-(IC5-BYPASS)") (class "Default")
      (node (ref "C19") (pin "1") (pinfunction "1_1") (pintype "passive"))
      (node (ref "IC5") (pin "4") (pinfunction "BYPASS_4") (pintype "bidirectional"))
    )
    (net (code "41") (name "Net-(R8-Pad2)") (class "Default")
      (node (ref "R8") (pin "2") (pinfunction "2_2") (pintype "passive"))
      (node (ref "SV2") (pin "2") (pinfunction "2_2") (pintype "passive"))
    )
    (net (code "42") (name "Net-(R14-Pad2)") (class "Default")
      (node (ref "R14") (pin "2") (pinfunction "2_2") (pintype "passive"))
      (node (ref "SV3") (pin "2") (pinfunction "2_2") (pintype "passive"))
    )
    (net (code "43") (name "SCK") (class "Default")
      (node (ref "IC2") (pin "25") (pinfunction "MCLK_25") (pintype "bidirectional"))
      (node (ref "R4") (pin "1") (pinfunction "1_1") (pintype "passive"))
      (node (ref "SV4") (pin "4") (pinfunction "4_4") (pintype "passive"))
    )
    (net (code "44") (name "unconnected-(IC1-ZEROA-Pad16)") (class "Default")
      (node (ref "IC1") (pin "16") (pinfunction "ZEROA_16") (pintype "bidirectional"))
    )
    (net (code "45") (name "unconnected-(IC2-GPIO.0-Pad30)") (class "Default")
      (node (ref "IC2") (pin "30") (pinfunction "GPIO.0_30") (pintype "bidirectional"))
    )
    (net (code "46") (name "unconnected-(IC2-GPIO.1-Pad29)") (class "Default")
      (node (ref "IC2") (pin "29") (pinfunction "GPIO.1_29") (pintype "bidirectional"))
    )
    (net (code "47") (name "unconnected-(IC2-GPIO.2-Pad14)") (class "Default")
      (node (ref "IC2") (pin "14") (pinfunction "GPIO.2_14") (pintype "bidirectional"))
    )
    (net (code "48") (name "unconnected-(IC2-GPIO.3-Pad13)") (class "Default")
      (node (ref "IC2") (pin "13") (pinfunction "GPIO.3_13") (pintype "bidirectional"))
    )
    (net (code "49") (name "unconnected-(IC2-GPIO.4-Pad12)") (class "Default")
      (node (ref "IC2") (pin "12") (pinfunction "GPIO.4_12") (pintype "bidirectional"))
    )
    (net (code "50") (name "unconnected-(IC2-GPIO.9-Pad22)") (class "Default")
      (node (ref "IC2") (pin "22") (pinfunction "GPIO.9_22") (pintype "bidirectional"))
    )
    (net (code "51") (name "unconnected-(IC2-GPIO.10-Pad16)") (class "Default")
      (node (ref "IC2") (pin "16") (pinfunction "GPIO.10_16") (pintype "bidirectional"))
    )
    (net (code "52") (name "unconnected-(IC2-GPIO.11-Pad15)") (class "Default")
      (node (ref "IC2") (pin "15") (pinfunction "GPIO.11_15") (pintype "bidirectional"))
    )
    (net (code "53") (name "unconnected-(IC2-~{SUSPEND}-Pad17)") (class "Default")
      (node (ref "IC2") (pin "17") (pinfunction "~{SUSPEND}_17") (pintype "bidirectional"))
    )
    (net (code "54") (name "unconnected-(SV2-Pad1)") (class "Default")
      (node (ref "SV2") (pin "1") (pinfunction "1_1") (pintype "passive"))
    )
    (net (code "55") (name "unconnected-(SV3-Pad1)") (class "Default")
      (node (ref "SV3") (pin "1") (pinfunction "1_1") (pintype "passive"))
    )
    (net (code "56") (name "unconnected-(X1-PadS1)") (class "Default")
      (node (ref "X1") (pin "S1") (pinfunction "S1_S1") (pintype "passive"))
    )
  )
)
